# sensornode_poc_rtc.net
KiCad netlist of a schematic drawn in Altium Designer
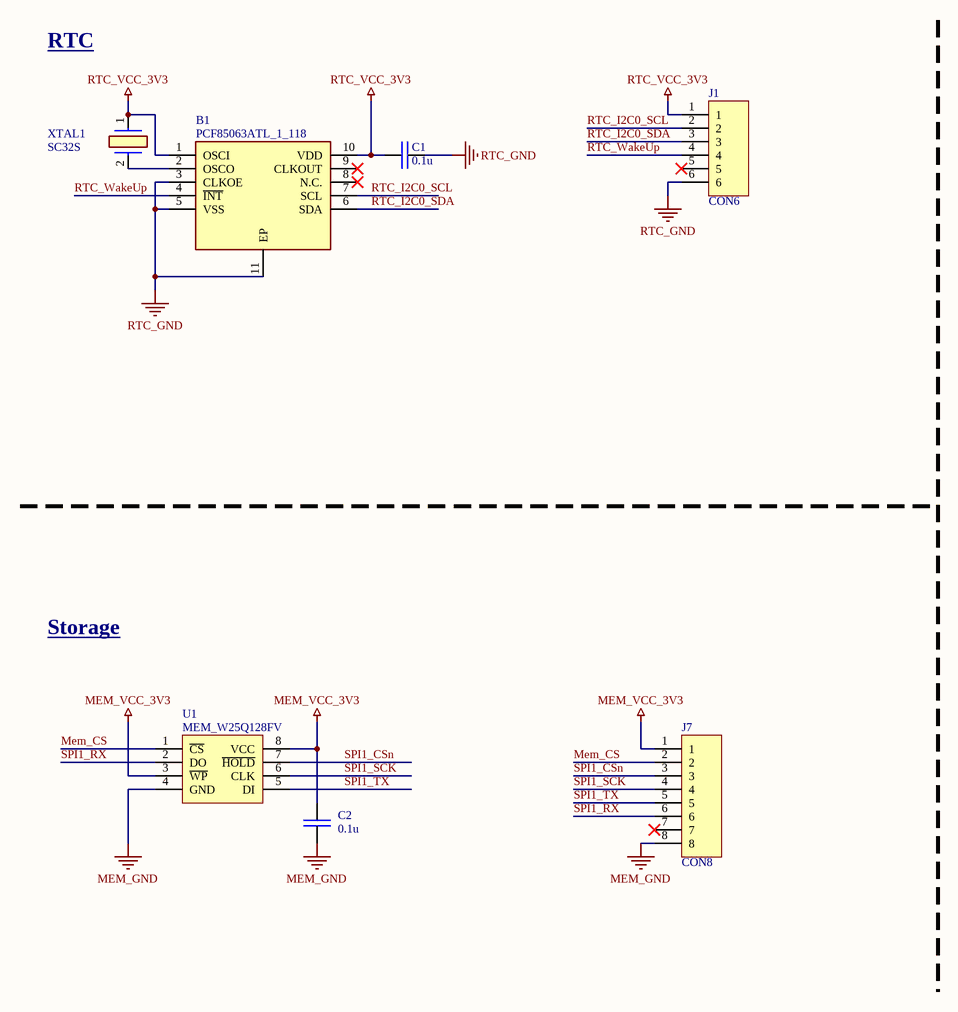
[diagram p0: sensornode_poc_rtc.SchDoc]

(export (version "E")
  (design (tool "Eeschema 10.0.6"))
  (components
    (comp (ref "B1")
      (value "PCF85063ATL_1_118")
      (footprint "SON50P260X260X50-11N")
      (description "NXP - PCF85063ATL/1,118 - REAL TIME CLOCK/CALENDAR, BINARY, HXSON")
      (fields
        (field (name "MOUSER PART NUMBER") "771-PCF85063ATL1118")
        (field (name "MANUFACTURER_PART_NUMBER") "PCF85063ATL/1,118")
      )
      (libsource (lib "sensornode") (part "PCF85063ATL_1_118"))
    )
    (comp (ref "C1")
      (value "0.1u")
      (footprint "AMZ_Altium_Lib:0805")
      (libsource (lib "AMZ_Altium_Lib") (part "C"))
    )
    (comp (ref "C2")
      (value "0.1u")
      (footprint "AMZ_Altium_Lib:0805")
      (libsource (lib "AMZ_Altium_Lib") (part "C"))
    )
    (comp (ref "J1")
      (value "CON6")
      (footprint "AMZ_Altium_Lib:CON_1x6_RM2.54_tht")
      (libsource (lib "AMZ_Altium_Lib") (part "CON6"))
    )
    (comp (ref "J7")
      (value "CON8")
      (footprint "AMZ_Altium_Lib:HEADER_8_RM_2.54")
      (libsource (lib "AMZ_Altium_Lib") (part "CON8"))
    )
    (comp (ref "U1")
      (value "MEM_W25Q128FV")
      (footprint "SamacSys:SON127P600X500X80-9N-D")
      (libsource (lib "vm2") (part "MEMORY_W25Q128FV"))
    )
    (comp (ref "XTAL1")
      (value "SC32S")
      (footprint "SamacSys:SC32S7PF20PPM")
      (description "Oscillator SC32S-7PF20PPM")
      (fields
        (field (name "MANUFACTURER_PART_NUMBER") "SC32S-7PF20PPM")
        (field (name "MOUSER PART NUMBER") "628-SC32S-7PF20PPM")
      )
      (libsource (lib "*") (part "SC32S-7PF20PPM"))
    )
  )
  (nets
    (net (code "1") (name "/Mem_CS") (class "Default")
      (node (ref "J7") (pin "2") (pinfunction "2_2") (pintype "passive"))
      (node (ref "U1") (pin "1") (pinfunction "CS_1") (pintype "passive"))
    )
    (net (code "2") (name "/RTC_I2C0_SCL") (class "Default")
      (node (ref "B1") (pin "7") (pinfunction "SCL_7") (pintype "passive"))
      (node (ref "J1") (pin "2") (pinfunction "2_2") (pintype "passive"))
    )
    (net (code "3") (name "/RTC_I2C0_SDA") (class "Default")
      (node (ref "B1") (pin "6") (pinfunction "SDA_6") (pintype "passive"))
      (node (ref "J1") (pin "3") (pinfunction "3_3") (pintype "passive"))
    )
    (net (code "4") (name "/RTC_WakeUp") (class "Default")
      (node (ref "B1") (pin "4") (pinfunction "~{INT}_4") (pintype "passive"))
      (node (ref "J1") (pin "4") (pinfunction "4_4") (pintype "passive"))
    )
    (net (code "5") (name "/SPI1_CSn") (class "Default")
      (node (ref "J7") (pin "3") (pinfunction "3_3") (pintype "passive"))
      (node (ref "U1") (pin "7") (pinfunction "HOLD_7") (pintype "passive"))
    )
    (net (code "6") (name "/SPI1_RX") (class "Default")
      (node (ref "J7") (pin "6") (pinfunction "6_6") (pintype "passive"))
      (node (ref "U1") (pin "2") (pinfunction "DO_2") (pintype "passive"))
    )
    (net (code "7") (name "/SPI1_SCK") (class "Default")
      (node (ref "J7") (pin "4") (pinfunction "4_4") (pintype "passive"))
      (node (ref "U1") (pin "6") (pinfunction "CLK_6") (pintype "passive"))
    )
    (net (code "8") (name "/SPI1_TX") (class "Default")
      (node (ref "J7") (pin "5") (pinfunction "5_5") (pintype "passive"))
      (node (ref "U1") (pin "5") (pinfunction "DI_5") (pintype "passive"))
    )
    (net (code "9") (name "MEM_GND") (class "Default")
      (node (ref "C2") (pin "2") (pinfunction "2_2") (pintype "passive"))
      (node (ref "J7") (pin "8") (pinfunction "8_8") (pintype "passive"))
      (node (ref "U1") (pin "4") (pinfunction "GND_4") (pintype "passive"))
    )
    (net (code "10") (name "MEM_VCC_3V3") (class "Default")
      (node (ref "C2") (pin "1") (pinfunction "1_1") (pintype "passive"))
      (node (ref "J7") (pin "1") (pinfunction "1_1") (pintype "passive"))
      (node (ref "U1") (pin "3") (pinfunction "WP_3") (pintype "passive"))
      (node (ref "U1") (pin "8") (pinfunction "VCC_8") (pintype "passive"))
    )
    (net (code "11") (name "Net-(B1-OSCO)") (class "Default")
      (node (ref "B1") (pin "2") (pinfunction "OSCO_2") (pintype "passive"))
      (node (ref "XTAL1") (pin "2") (pinfunction "2_2") (pintype "passive"))
    )
    (net (code "12") (name "RTC_GND") (class "Default")
      (node (ref "B1") (pin "11") (pinfunction "EP_11") (pintype "passive"))
      (node (ref "B1") (pin "3") (pinfunction "CLKOE_3") (pintype "passive"))
      (node (ref "B1") (pin "5") (pinfunction "VSS_5") (pintype "passive"))
      (node (ref "C1") (pin "2") (pinfunction "2_2") (pintype "passive"))
      (node (ref "J1") (pin "6") (pinfunction "6_6") (pintype "passive"))
    )
    (net (code "13") (name "RTC_VCC_3V3") (class "Default")
      (node (ref "B1") (pin "1") (pinfunction "OSCI_1") (pintype "passive"))
      (node (ref "B1") (pin "10") (pinfunction "VDD_10") (pintype "passive"))
      (node (ref "C1") (pin "1") (pinfunction "1_1") (pintype "passive"))
      (node (ref "J1") (pin "1") (pinfunction "1_1") (pintype "passive"))
      (node (ref "XTAL1") (pin "1") (pinfunction "1_1") (pintype "passive"))
    )
    (net (code "14") (name "unconnected-(B1-CLKOUT-Pad9)") (class "Default")
      (node (ref "B1") (pin "9") (pinfunction "CLKOUT_9") (pintype "passive+no_connect"))
    )
    (net (code "15") (name "unconnected-(B1-N.C.-Pad8)") (class "Default")
      (node (ref "B1") (pin "8") (pinfunction "N.C._8") (pintype "passive+no_connect"))
    )
    (net (code "16") (name "unconnected-(J1-Pad5)") (class "Default")
      (node (ref "J1") (pin "5") (pinfunction "5_5") (pintype "passive+no_connect"))
    )
    (net (code "17") (name "unconnected-(J7-Pad7)") (class "Default")
      (node (ref "J7") (pin "7") (pinfunction "7_7") (pintype "passive+no_connect"))
    )
  )
)
